# ST_LINK_V2-1.net
KiCad netlist of a schematic drawn in Altium Designer
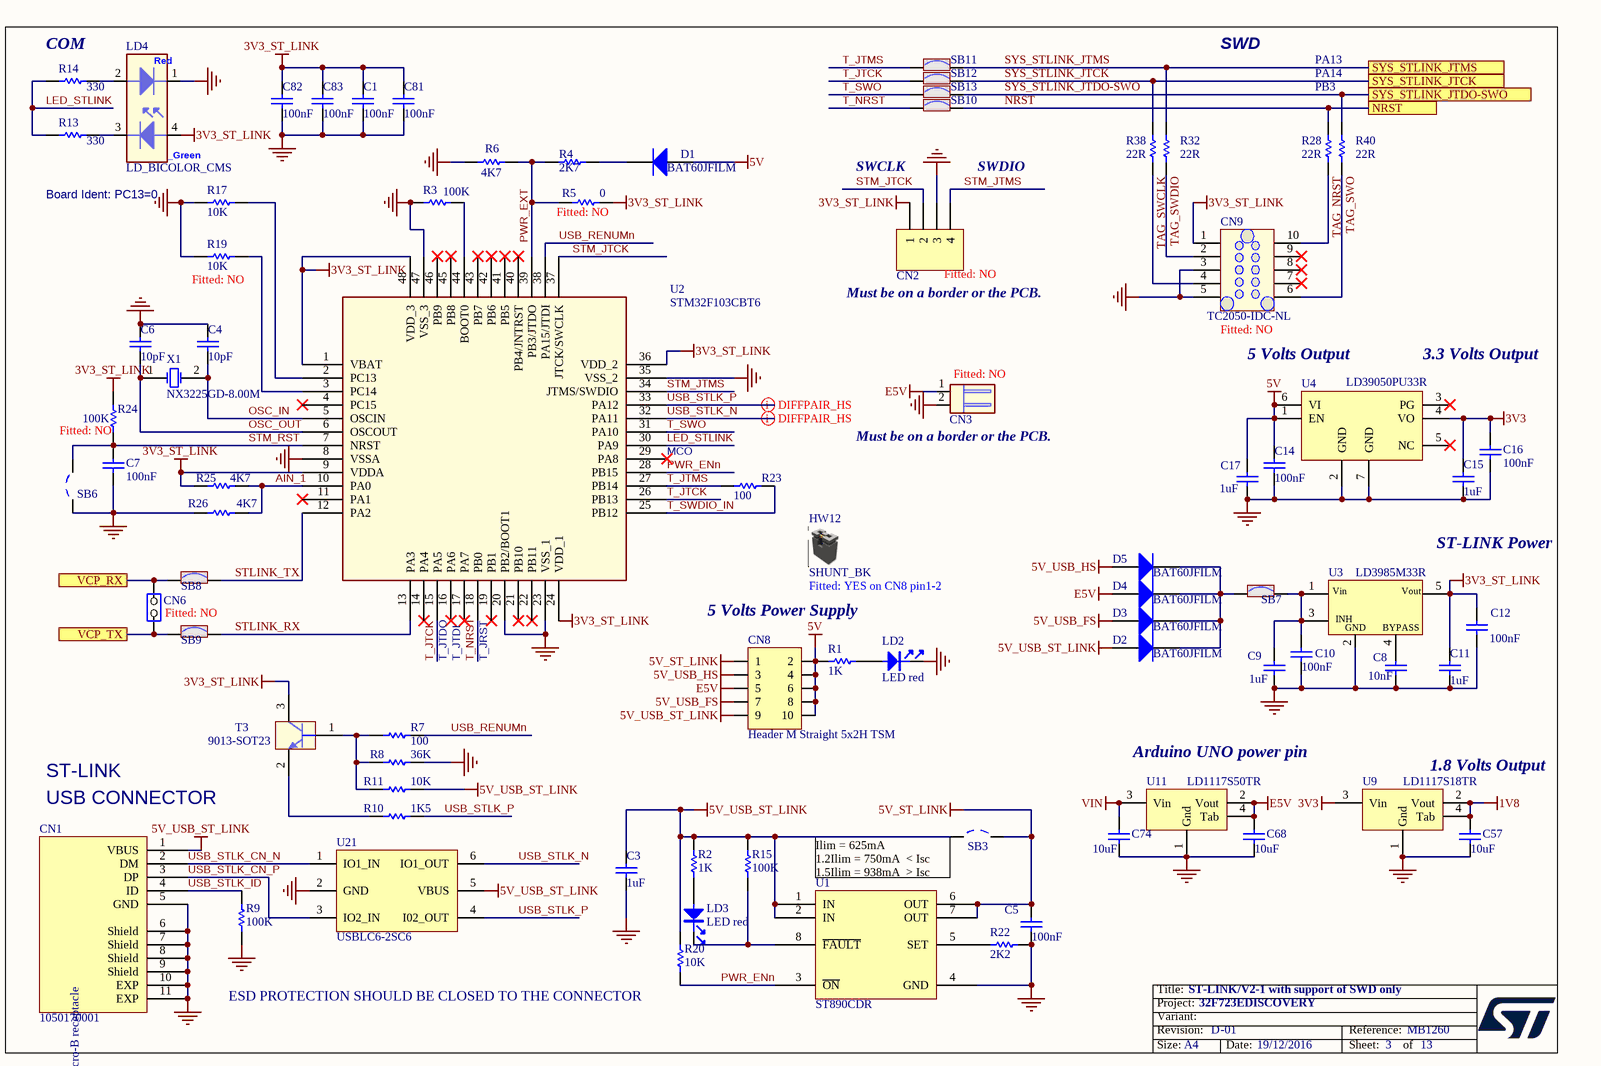
[diagram p0: ST_LINK_V2-1.SCHDOC]

(export (version "E")
  (design (tool "Eeschema 10.0.6"))
  (components
    (comp (ref "C1")
      (value "100nF")
      (footprint "0402C")
      (description "Capacitor,100nF,16V,X7R,10%,0402,YAGEO")
      (libsource (lib "MCD_TOOLS") (part "Cap_100nF_X7R_10%_0402"))
    )
    (comp (ref "C3")
      (value "1uF")
      (footprint "0603C")
      (description "Capacitor,1uF,16V,X5R,10%,0603,YAGEO")
      (libsource (lib "MCD_TOOLS_CAPACITOR") (part "Cap_1uF_X5R_10%_0603"))
    )
    (comp (ref "C4")
      (value "10pF")
      (footprint "0402C")
      (description "Capacitor,10pF,50V,NPO,5%,0402,YAGEO")
      (libsource (lib "MCD_TOOLS") (part "Cap_10pF_NPO_5%_0402"))
    )
    (comp (ref "C5")
      (value "100nF")
      (footprint "0402C")
      (description "Capacitor,100nF,16V,X7R,10%,0402,YAGEO")
      (libsource (lib "MCD_TOOLS") (part "Cap_100nF_X7R_10%_0402"))
    )
    (comp (ref "C6")
      (value "10pF")
      (footprint "0402C")
      (description "Capacitor,10pF,50V,NPO,5%,0402,YAGEO")
      (libsource (lib "MCD_TOOLS") (part "Cap_10pF_NPO_5%_0402"))
    )
    (comp (ref "C7")
      (value "100nF")
      (footprint "0402C")
      (description "Capacitor,100nF,16V,X7R,10%,0402,YAGEO")
      (libsource (lib "MCD_TOOLS") (part "Cap_100nF_X7R_10%_0402"))
    )
    (comp (ref "C8")
      (value "10nF")
      (footprint "0603C")
      (description "Capacitor,10nF,50V,X7R,10%,0603,YAGEO")
      (fields (field (name "Comment") "10nF_X7R_10%_0603"))
      (libsource (lib "MCD_TOOLS_CAPACITOR") (part "Cap_10nF_X7R_10%_0603"))
    )
    (comp (ref "C9")
      (value "1uF")
      (footprint "0603C")
      (description "Capacitor,1uF,16V,X5R,10%,0603,YAGEO")
      (libsource (lib "MCD_TOOLS_CAPACITOR") (part "Cap_1uF_X5R_10%_0603"))
    )
    (comp (ref "C10")
      (value "100nF")
      (footprint "0402C")
      (description "Capacitor,100nF,16V,X7R,10%,0402,YAGEO")
      (libsource (lib "MCD_TOOLS") (part "Cap_100nF_X7R_10%_0402"))
    )
    (comp (ref "C11")
      (value "1uF")
      (footprint "0603C")
      (description "Capacitor,1uF,16V,X5R,10%,0603,YAGEO")
      (libsource (lib "MCD_TOOLS_CAPACITOR") (part "Cap_1uF_X5R_10%_0603"))
    )
    (comp (ref "C12")
      (value "100nF")
      (footprint "0402C")
      (description "Capacitor,100nF,16V,X7R,10%,0402,YAGEO")
      (libsource (lib "MCD_TOOLS") (part "Cap_100nF_X7R_10%_0402"))
    )
    (comp (ref "C14")
      (value "100nF")
      (footprint "0402C")
      (description "Capacitor,100nF,16V,X7R,10%,0402,YAGEO")
      (libsource (lib "MCD_TOOLS") (part "Cap_100nF_X7R_10%_0402"))
    )
    (comp (ref "C15")
      (value "1uF")
      (footprint "0603C")
      (description "Capacitor,1uF,16V,X5R,10%,0603,YAGEO")
      (libsource (lib "MCD_TOOLS_CAPACITOR") (part "Cap_1uF_X5R_10%_0603"))
    )
    (comp (ref "C16")
      (value "100nF")
      (footprint "0402C")
      (description "Capacitor,100nF,16V,X7R,10%,0402,YAGEO")
      (libsource (lib "MCD_TOOLS") (part "Cap_100nF_X7R_10%_0402"))
    )
    (comp (ref "C17")
      (value "1uF")
      (footprint "0603C")
      (description "Capacitor,1uF,16V,X5R,10%,0603,YAGEO")
      (libsource (lib "MCD_TOOLS_CAPACITOR") (part "Cap_1uF_X5R_10%_0603"))
    )
    (comp (ref "C57")
      (value "10uF")
      (footprint "0603C")
      (description "Capacitor,10uF,6.3V,X5R,10%,0603,YAGEO")
      (libsource (lib "MCD_TOOLS") (part "Cap_10uF_X5R_10%_0603"))
    )
    (comp (ref "C68")
      (value "10uF")
      (footprint "0805C")
      (description "Capacitor,10uF,25V,X5R,10%,0805,YAGEO")
      (libsource (lib "MCD_TOOLS") (part "Cap_10uF_X5R_10%_0805"))
    )
    (comp (ref "C74")
      (value "10uF")
      (footprint "0805C")
      (description "Capacitor,10uF,25V,X5R,10%,0805,YAGEO")
      (libsource (lib "MCD_TOOLS") (part "Cap_10uF_X5R_10%_0805"))
    )
    (comp (ref "C81")
      (value "100nF")
      (footprint "0402C")
      (description "Capacitor,100nF,16V,X7R,10%,0402,YAGEO")
      (libsource (lib "MCD_TOOLS") (part "Cap_100nF_X7R_10%_0402"))
    )
    (comp (ref "C82")
      (value "100nF")
      (footprint "0402C")
      (description "Capacitor,100nF,16V,X7R,10%,0402,YAGEO")
      (libsource (lib "MCD_TOOLS") (part "Cap_100nF_X7R_10%_0402"))
    )
    (comp (ref "C83")
      (value "100nF")
      (footprint "0402C")
      (description "Capacitor,100nF,16V,X7R,10%,0402,YAGEO")
      (libsource (lib "MCD_TOOLS") (part "Cap_100nF_X7R_10%_0402"))
    )
    (comp (ref "CN1")
      (value "1050170001")
      (footprint "MICRO_USB_B_105017")
      (description "USB-MICRO-B, 1050170001, SMT, MOLEX")
      (libsource (lib "MCD_TEMP_NPA") (part "1050170001"))
    )
    (comp (ref "CN2")
      (value "Header 4")
      (footprint "HDR_1X4_2R54")
      (description "Header, 4-Pin")
      (fields (field (name "FITTED") "NO") (field (name "PUBLISHER") "Altium Limited"))
      (libsource (lib "MCD_TOOLS_CONNECTOR") (part "Header 4"))
    )
    (comp (ref "CN3")
      (value "WF25402-06421")
      (footprint "HDR_1X2_2R54_RA_11R35")
      (description "Header, 2-Pins, Single row, Right Angle, 2.54 mm pitch, DIP")
      (fields (field (name "FITTED") "NO"))
      (libsource (lib "MCD_TOOLS_CONNECTOR") (part "JP2_RA"))
    )
    (comp (ref "CN6")
      (value "JP2")
      (footprint "SIP2")
      (fields (field (name "FITTED") "NO"))
      (libsource (lib "MCD_TOOLS_CONNECTOR") (part "JP2"))
    )
    (comp (ref "CN8")
      (value "Header M Straight 5x2H TSM")
      (footprint "TSM-105-01-S-DV")
      (description "Header Male TSM, 5-Pin, Dual row, Straight, AMD")
      (libsource (lib "MCD_TEMP_NPA") (part "Header 5X2M TSM"))
    )
    (comp (ref "CN9")
      (value "TC2050-IDC-NL")
      (footprint "TC2050-IDC-NL")
      (description "Tag_Connector Header, 10-Pin, Dual row No legs")
      (fields (field (name "FITTED") "NO"))
      (libsource (lib "MCD_TEMP_PCH") (part "Tag-10-C"))
    )
    (comp (ref "D1")
      (value "BAT60JFILM")
      (footprint "SOD-323")
      (libsource (lib "MCD_TOOLS_MISCELLANEOUS") (part "BAT60JFILM"))
    )
    (comp (ref "D2")
      (value "BAT60JFILM")
      (footprint "SOD-323")
      (libsource (lib "MCD_TOOLS_MISCELLANEOUS") (part "BAT60JFILM"))
    )
    (comp (ref "D3")
      (value "BAT60JFILM")
      (footprint "SOD-323")
      (libsource (lib "MCD_TOOLS_MISCELLANEOUS") (part "BAT60JFILM"))
    )
    (comp (ref "D4")
      (value "BAT60JFILM")
      (footprint "SOD-323")
      (libsource (lib "MCD_TOOLS_MISCELLANEOUS") (part "BAT60JFILM"))
    )
    (comp (ref "D5")
      (value "BAT60JFILM")
      (footprint "SOD-323")
      (libsource (lib "MCD_TOOLS_MISCELLANEOUS") (part "BAT60JFILM"))
    )
    (comp (ref "HW12")
      (value "SHUNT_BK")
      (description "SHUNT 2.54mm BLACK")
      (fields (field (name "FITTED") "YES on CN8 pin1-2"))
      (libsource (lib "MCD_Temp_LBE") (part "Shunt 2.54mm"))
    )
    (comp (ref "LD2")
      (value "LED red")
      (footprint "0603D")
      (description "LED red 0603")
      (libsource (lib "MCD_TEMP_NPA") (part "LED_red"))
    )
    (comp (ref "LD3")
      (value "LED red")
      (footprint "0603D")
      (description "LED red 0603")
      (libsource (lib "MCD_TEMP_NPA") (part "LED_red"))
    )
    (comp (ref "LD4")
      (value "LD_BICOLOR_CMS")
      (footprint "LED2_3528")
      (description "Bicolor Led")
      (libsource (lib "MCD_TOOLS_MISCELLANEOUS") (part "LD_BICOLOR_CMS"))
    )
    (comp (ref "R1")
      (value "1K")
      (footprint "0402R")
      (description "Resistor,1K,0402,1%,YAGEO")
      (libsource (lib "MCD_TOOLS_RESISTOR") (part "Res_1K_1%_0402"))
    )
    (comp (ref "R2")
      (value "1K")
      (footprint "0402R")
      (description "Resistor,1K,0402,1%,YAGEO")
      (libsource (lib "MCD_TOOLS_RESISTOR") (part "Res_1K_1%_0402"))
    )
    (comp (ref "R3")
      (value "100K")
      (footprint "0402R")
      (description "Resistor,100K,0402,1%,YAGEO")
      (fields (field (name "Comment") "100K_1%_0402"))
      (libsource (lib "MCD_TOOLS_RESISTOR") (part "Res_100K_1%_0402"))
    )
    (comp (ref "R4")
      (value "2K7")
      (footprint "0402R")
      (description "Resistor,2K7,0402,1%,YAGEO")
      (libsource (lib "MCD_TOOLS") (part "Res_2K7_1%_0402"))
    )
    (comp (ref "R5")
      (value "0")
      (footprint "0402R")
      (description "Resistor,0,0402,5%,YAGEO")
      (fields (field (name "FITTED") "NO"))
      (libsource (lib "MCD_TOOLS") (part "Res_0_5%_0402"))
    )
    (comp (ref "R6")
      (value "4K7")
      (footprint "0402R")
      (description "Resistor,4K7,0402,1%,YAGEO")
      (fields (field (name "Comment") "4K7_1%_0402"))
      (libsource (lib "MCD_TOOLS_RESISTOR") (part "Res_4K7_1%_0402"))
    )
    (comp (ref "R7")
      (value "100")
      (footprint "0402R")
      (description "Resistor,100,0402,1%,YAGEO")
      (libsource (lib "MCD_TOOLS") (part "Res_100_1%_0402"))
    )
    (comp (ref "R8")
      (value "36K")
      (footprint "0402R")
      (description "Resistor,36K,0402,1%,YAGEO")
      (libsource (lib "MCD_TOOLS") (part "Res_36K_1%_0402"))
    )
    (comp (ref "R9")
      (value "100K")
      (footprint "0402R")
      (description "Resistor,100K,0402,1%,YAGEO")
      (fields (field (name "Comment") "100K_1%_0402"))
      (libsource (lib "MCD_TOOLS_RESISTOR") (part "Res_100K_1%_0402"))
    )
    (comp (ref "R10")
      (value "1K5")
      (footprint "0402R")
      (description "Resistor,1K5,0402,1%,YAGEO")
      (libsource (lib "MCD_TOOLS") (part "Res_1K5_1%_0402"))
    )
    (comp (ref "R11")
      (value "10K")
      (footprint "0402R")
      (description "Resistor,10K,0402,1%,YAGEO")
      (libsource (lib "MCD_TOOLS") (part "Res_10K_1%_0402"))
    )
    (comp (ref "R13")
      (value "330")
      (footprint "0402R")
      (description "Resistor,330,0402,1%,YAGEO")
      (libsource (lib "MCD_TOOLS") (part "Res_330_1%_0402"))
    )
    (comp (ref "R14")
      (value "330")
      (footprint "0402R")
      (description "Resistor,330,0402,1%,YAGEO")
      (libsource (lib "MCD_TOOLS") (part "Res_330_1%_0402"))
    )
    (comp (ref "R15")
      (value "100K")
      (footprint "0402R")
      (description "Resistor,100K,0402,1%,YAGEO")
      (fields (field (name "Comment") "100K_1%_0402"))
      (libsource (lib "MCD_TOOLS_RESISTOR") (part "Res_100K_1%_0402"))
    )
    (comp (ref "R17")
      (value "10K")
      (footprint "0402R")
      (description "Resistor,10K,0402,1%,YAGEO")
      (libsource (lib "MCD_TOOLS") (part "Res_10K_1%_0402"))
    )
    (comp (ref "R19")
      (value "10K")
      (footprint "0402R")
      (description "Resistor,10K,0402,1%,YAGEO")
      (fields (field (name "FITTED") "NO"))
      (libsource (lib "MCD_TOOLS") (part "Res_10K_1%_0402"))
    )
    (comp (ref "R20")
      (value "10K")
      (footprint "0402R")
      (description "Resistor,10K,0402,1%,YAGEO")
      (libsource (lib "MCD_TOOLS") (part "Res_10K_1%_0402"))
    )
    (comp (ref "R22")
      (value "2K2")
      (footprint "0402R")
      (description "Resistor,2K2,0402,1%,YAGEO")
      (libsource (lib "MCD_TOOLS_RESISTOR") (part "Res_2K2_1%_0402"))
    )
    (comp (ref "R23")
      (value "100")
      (footprint "0402R")
      (description "Resistor,100,0402,1%,YAGEO")
      (libsource (lib "MCD_TOOLS") (part "Res_100_1%_0402"))
    )
    (comp (ref "R24")
      (value "100K")
      (footprint "0402R")
      (description "Resistor,100K,0402,1%,YAGEO")
      (fields (field (name "FITTED") "NO") (field (name "Comment") "100K_1%_0402"))
      (libsource (lib "MCD_TOOLS_RESISTOR") (part "Res_100K_1%_0402"))
    )
    (comp (ref "R25")
      (value "4K7")
      (footprint "0402R")
      (description "Resistor,4K7,0402,1%,YAGEO")
      (fields (field (name "Comment") "4K7_1%_0402"))
      (libsource (lib "MCD_TOOLS_RESISTOR") (part "Res_4K7_1%_0402"))
    )
    (comp (ref "R26")
      (value "4K7")
      (footprint "0402R")
      (description "Resistor,4K7,0402,1%,YAGEO")
      (fields (field (name "Comment") "4K7_1%_0402"))
      (libsource (lib "MCD_TOOLS_RESISTOR") (part "Res_4K7_1%_0402"))
    )
    (comp (ref "R28")
      (value "22R")
      (footprint "R0603")
      (description "Resistor,22R,0603,1%,Yageo")
      (libsource (lib "MCD_TEMP_PCH") (part "Res_22_1%_0603"))
    )
    (comp (ref "R32")
      (value "22R")
      (footprint "R0603")
      (description "Resistor,22R,0603,1%,Yageo")
      (libsource (lib "MCD_TEMP_PCH") (part "Res_22_1%_0603"))
    )
    (comp (ref "R38")
      (value "22R")
      (footprint "R0603")
      (description "Resistor,22R,0603,1%,Yageo")
      (libsource (lib "MCD_TEMP_PCH") (part "Res_22_1%_0603"))
    )
    (comp (ref "R40")
      (value "22R")
      (footprint "R0603")
      (description "Resistor,22R,0603,1%,Yageo")
      (libsource (lib "MCD_TEMP_PCH") (part "Res_22_1%_0603"))
    )
    (comp (ref "SB3")
      (value "Solder Bridge OFF")
      (footprint "JP2_SMD")
      (libsource (lib "MCD_TOOLS") (part "SB_OFF"))
    )
    (comp (ref "SB6")
      (value "Solder Bridge OFF")
      (footprint "JP2_SMD")
      (libsource (lib "MCD_TOOLS") (part "SB_OFF"))
    )
    (comp (ref "SB7")
      (value "Solder Bridge ON")
      (footprint "JP2_SMD")
      (libsource (lib "MCD_TOOLS") (part "SB_ON"))
    )
    (comp (ref "SB8")
      (value "Solder Bridge ON")
      (footprint "JP2_SMD")
      (libsource (lib "MCD_TOOLS") (part "SB_ON"))
    )
    (comp (ref "SB9")
      (value "Solder Bridge ON")
      (footprint "JP2_SMD")
      (libsource (lib "MCD_TOOLS") (part "SB_ON"))
    )
    (comp (ref "SB10")
      (value "Solder Bridge ON")
      (footprint "JP2_SMD")
      (libsource (lib "MCD_TOOLS") (part "SB_ON"))
    )
    (comp (ref "SB11")
      (value "Solder Bridge ON")
      (footprint "JP2_SMD")
      (libsource (lib "MCD_TOOLS") (part "SB_ON"))
    )
    (comp (ref "SB12")
      (value "Solder Bridge ON")
      (footprint "JP2_SMD")
      (libsource (lib "MCD_TOOLS") (part "SB_ON"))
    )
    (comp (ref "SB13")
      (value "Solder Bridge ON")
      (footprint "JP2_SMD")
      (libsource (lib "MCD_TOOLS") (part "SB_ON"))
    )
    (comp (ref "T3")
      (value "9013-SOT23")
      (footprint "SOT-23")
      (description "NPN Bipolar Transistor")
      (libsource (lib "MCD_TOOLS_MISCELLANEOUS") (part "9013-SOT23"))
    )
    (comp (ref "U1")
      (value "ST890CDR")
      (footprint "SOIC8_1R27_4R9X6")
      (description "1.2 A current limited high-side power switch with thermal shutdown")
      (libsource (lib "MCD_TEMP_NPA") (part "ST890CDR"))
    )
    (comp (ref "U2")
      (value "STM32F103CBT6")
      (footprint "LQFP48_0R5_9X9")
      (description "Medium-density performance line ARM-based 32-bit MCU with 128KB Flash")
      (libsource (lib "MCD_TOOLS_MCU") (part "STM32F103CBT6"))
    )
    (comp (ref "U3")
      (value "LD3985M33R")
      (footprint "SOT-23-5L")
      (description "Ultra low drop-low noise BiCMOS voltage, regulators low ESR capacitors compatible")
      (libsource (lib "MCD_TOOLS_MISCELLANEOUS") (part "LD3985M33R"))
    )
    (comp (ref "U4")
      (value "LD39050PU33R")
      (footprint "DFN6_0R95_3X3")
      (description "Ultra low drop-low , 500 mA low quiescent current")
      (libsource (lib "MCD_TEMP_NPA") (part "LD39050P"))
    )
    (comp (ref "U9")
      (value "LD1117S18TR")
      (footprint "SOT-223")
      (description "LOW DROP FIXED AND ADJUSTABLE POSITIVE VOLTAGE REGULATORS (1.8 Volts)")
      (libsource (lib "MCD_TEMP_NPA") (part "LD1117S18TR"))
    )
    (comp (ref "U11")
      (value "LD1117S50TR")
      (footprint "SOT-223")
      (description "IC REG LDO 5V 0.8A SOT223")
      (libsource (lib "MCD_TEMP_NPA") (part "LD1117S50TR"))
    )
    (comp (ref "U21")
      (value "USBLC6-2SC6")
      (footprint "SOT23-6")
      (description "Very low capacitance ESD protection")
      (libsource (lib "MCD_TEMP_NPA") (part "USBLC6-2SC6"))
    )
    (comp (ref "X1")
      (value "NX3225GD-8.00M")
      (footprint "XTAL_2SM_3R2X2R5_H1")
      (description "Crystal 8Mhz, 8pF, -+50PPM, SMD")
      (libsource (lib "MCD_TEMP_NPA") (part "XTAL_8M_NX3225GD"))
    )
  )
  (nets
    (net (code "1") (name "/AIN_1") (class "Default")
      (node (ref "R25") (pin "2") (pinfunction "2_2") (pintype "passive"))
      (node (ref "R26") (pin "2") (pinfunction "2_2") (pintype "passive"))
      (node (ref "U2") (pin "10") (pinfunction "PA0_10") (pintype "passive"))
    )
    (net (code "2") (name "/LED_STLINK") (class "Default")
      (node (ref "R13") (pin "1") (pinfunction "1_1") (pintype "passive"))
      (node (ref "R14") (pin "1") (pinfunction "1_1") (pintype "passive"))
      (node (ref "U2") (pin "30") (pinfunction "PA9_30") (pintype "passive"))
    )
    (net (code "3") (name "/NRST") (class "Default")
      (node (ref "R28") (pin "2") (pinfunction "2_2") (pintype "passive"))
      (node (ref "SB10") (pin "2") (pinfunction "2_2") (pintype "passive"))
    )
    (net (code "4") (name "/OSC_IN") (class "Default")
      (node (ref "C4") (pin "2") (pinfunction "2_2") (pintype "passive"))
      (node (ref "U2") (pin "5") (pinfunction "OSCIN_5") (pintype "passive"))
      (node (ref "X1") (pin "2") (pinfunction "OSC2_2") (pintype "passive"))
    )
    (net (code "5") (name "/OSC_OUT") (class "Default")
      (node (ref "C6") (pin "2") (pinfunction "2_2") (pintype "passive"))
      (node (ref "U2") (pin "6") (pinfunction "OSCOUT_6") (pintype "passive"))
      (node (ref "X1") (pin "1") (pinfunction "OSC1_1") (pintype "passive"))
    )
    (net (code "6") (name "/PWR_ENn") (class "Default")
      (node (ref "R20") (pin "1") (pinfunction "1_1") (pintype "passive"))
      (node (ref "U1") (pin "3") (pinfunction "~{ON}_3") (pintype "passive"))
      (node (ref "U2") (pin "28") (pinfunction "PB15_28") (pintype "passive"))
    )
    (net (code "7") (name "/PWR_EXT") (class "Default")
      (node (ref "R4") (pin "1") (pinfunction "1_1") (pintype "passive"))
      (node (ref "R5") (pin "1") (pinfunction "1_1") (pintype "passive"))
      (node (ref "R6") (pin "2") (pinfunction "2_2") (pintype "passive"))
      (node (ref "U2") (pin "39") (pinfunction "PB3/JTDO_39") (pintype "passive"))
    )
    (net (code "8") (name "/STLINK_RX") (class "Default")
      (node (ref "SB9") (pin "2") (pinfunction "2_2") (pintype "passive"))
      (node (ref "U2") (pin "13") (pinfunction "PA3_13") (pintype "passive"))
    )
    (net (code "9") (name "/STLINK_TX") (class "Default")
      (node (ref "SB8") (pin "2") (pinfunction "2_2") (pintype "passive"))
      (node (ref "U2") (pin "12") (pinfunction "PA2_12") (pintype "passive"))
    )
    (net (code "10") (name "/STM_JTCK") (class "Default")
      (node (ref "CN2") (pin "2") (pinfunction "2_2") (pintype "passive"))
      (node (ref "U2") (pin "37") (pinfunction "JTCK/SWCLK_37") (pintype "passive"))
    )
    (net (code "11") (name "/STM_JTMS") (class "Default")
      (node (ref "CN2") (pin "4") (pinfunction "4_4") (pintype "passive"))
      (node (ref "U2") (pin "34") (pinfunction "JTMS/SWDIO_34") (pintype "passive"))
    )
    (net (code "12") (name "/STM_RST") (class "Default")
      (node (ref "C7") (pin "2") (pinfunction "2_2") (pintype "passive"))
      (node (ref "R24") (pin "1") (pinfunction "1_1") (pintype "passive"))
      (node (ref "SB6") (pin "2") (pinfunction "2_2") (pintype "passive"))
      (node (ref "U2") (pin "7") (pinfunction "NRST_7") (pintype "passive"))
    )
    (net (code "13") (name "/SYS_STLINK_JTCK") (class "Default")
      (node (ref "R38") (pin "2") (pinfunction "2_2") (pintype "passive"))
      (node (ref "SB12") (pin "2") (pinfunction "2_2") (pintype "passive"))
    )
    (net (code "14") (name "/SYS_STLINK_JTDO-SWO") (class "Default")
      (node (ref "R40") (pin "2") (pinfunction "2_2") (pintype "passive"))
      (node (ref "SB13") (pin "2") (pinfunction "2_2") (pintype "passive"))
    )
    (net (code "15") (name "/SYS_STLINK_JTMS") (class "Default")
      (node (ref "R32") (pin "2") (pinfunction "2_2") (pintype "passive"))
      (node (ref "SB11") (pin "2") (pinfunction "2_2") (pintype "passive"))
    )
    (net (code "16") (name "/TAG_NRST") (class "Default")
      (node (ref "CN9") (pin "10") (pinfunction "10_10") (pintype "passive"))
      (node (ref "R28") (pin "1") (pinfunction "1_1") (pintype "passive"))
    )
    (net (code "17") (name "/TAG_SWCLK") (class "Default")
      (node (ref "CN9") (pin "4") (pinfunction "4_4") (pintype "passive"))
      (node (ref "R38") (pin "1") (pinfunction "1_1") (pintype "passive"))
    )
    (net (code "18") (name "/TAG_SWDIO") (class "Default")
      (node (ref "CN9") (pin "2") (pinfunction "2_2") (pintype "passive"))
      (node (ref "R32") (pin "1") (pinfunction "1_1") (pintype "passive"))
    )
    (net (code "19") (name "/TAG_SWO") (class "Default")
      (node (ref "CN9") (pin "6") (pinfunction "6_6") (pintype "passive"))
      (node (ref "R40") (pin "1") (pinfunction "1_1") (pintype "passive"))
    )
    (net (code "20") (name "/T_JTCK") (class "Default")
      (node (ref "SB12") (pin "1") (pinfunction "1_1") (pintype "passive"))
      (node (ref "U2") (pin "15") (pinfunction "PA5_15") (pintype "passive"))
      (node (ref "U2") (pin "26") (pinfunction "PB13_26") (pintype "passive"))
    )
    (net (code "21") (name "/T_JTMS") (class "Default")
      (node (ref "R23") (pin "1") (pinfunction "1_1") (pintype "passive"))
      (node (ref "SB11") (pin "1") (pinfunction "1_1") (pintype "passive"))
      (node (ref "U2") (pin "27") (pinfunction "PB14_27") (pintype "passive"))
    )
    (net (code "22") (name "/T_NRST") (class "Default")
      (node (ref "SB10") (pin "1") (pinfunction "1_1") (pintype "passive"))
      (node (ref "U2") (pin "18") (pinfunction "PB0_18") (pintype "passive"))
    )
    (net (code "23") (name "/T_SWDIO_IN") (class "Default")
      (node (ref "R23") (pin "2") (pinfunction "2_2") (pintype "passive"))
      (node (ref "U2") (pin "25") (pinfunction "PB12_25") (pintype "passive"))
    )
    (net (code "24") (name "/T_SWO") (class "Default")
      (node (ref "SB13") (pin "1") (pinfunction "1_1") (pintype "passive"))
      (node (ref "U2") (pin "31") (pinfunction "PA10_31") (pintype "passive"))
    )
    (net (code "25") (name "/USB_RENUMn") (class "Default")
      (node (ref "R7") (pin "2") (pinfunction "2_2") (pintype "passive"))
      (node (ref "U2") (pin "38") (pinfunction "PA15/JTDI_38") (pintype "passive"))
    )
    (net (code "26") (name "/USB_STLK_CN_N") (class "Default")
      (node (ref "CN1") (pin "2") (pinfunction "DM_2") (pintype "passive"))
      (node (ref "U21") (pin "1") (pinfunction "IO1_IN_1") (pintype "passive"))
    )
    (net (code "27") (name "/USB_STLK_CN_P") (class "Default")
      (node (ref "CN1") (pin "3") (pinfunction "DP_3") (pintype "passive"))
      (node (ref "U21") (pin "3") (pinfunction "IO2_IN_3") (pintype "passive"))
    )
    (net (code "28") (name "/USB_STLK_ID") (class "Default")
      (node (ref "CN1") (pin "4") (pinfunction "ID_4") (pintype "passive"))
      (node (ref "R9") (pin "2") (pinfunction "2_2") (pintype "passive"))
    )
    (net (code "29") (name "/USB_STLK_N") (class "Default")
      (node (ref "U2") (pin "32") (pinfunction "PA11_32") (pintype "passive"))
      (node (ref "U21") (pin "6") (pinfunction "IO1_OUT_6") (pintype "passive"))
    )
    (net (code "30") (name "/USB_STLK_P") (class "Default")
      (node (ref "R10") (pin "2") (pinfunction "2_2") (pintype "passive"))
      (node (ref "U2") (pin "33") (pinfunction "PA12_33") (pintype "passive"))
      (node (ref "U21") (pin "4") (pinfunction "I02_OUT_4") (pintype "passive"))
    )
    (net (code "31") (name "/VCP_RX") (class "Default")
      (node (ref "CN6") (pin "2") (pinfunction "NO_2") (pintype "passive"))
      (node (ref "SB8") (pin "1") (pinfunction "1_1") (pintype "passive"))
    )
    (net (code "32") (name "/VCP_TX") (class "Default")
      (node (ref "CN6") (pin "1") (pinfunction "COMMON_1") (pintype "passive"))
      (node (ref "SB9") (pin "1") (pinfunction "1_1") (pintype "passive"))
    )
    (net (code "33") (name "1V8") (class "Default")
      (node (ref "C57") (pin "2") (pinfunction "2_2") (pintype "passive"))
      (node (ref "U9") (pin "2") (pinfunction "Vout_2") (pintype "passive"))
      (node (ref "U9") (pin "4") (pinfunction "Tab_4") (pintype "passive"))
    )
    (net (code "34") (name "3V3") (class "Default")
      (node (ref "C15") (pin "2") (pinfunction "2_2") (pintype "passive"))
      (node (ref "C16") (pin "2") (pinfunction "2_2") (pintype "passive"))
      (node (ref "U4") (pin "4") (pinfunction "VO_4") (pintype "passive"))
      (node (ref "U9") (pin "3") (pinfunction "Vin_3") (pintype "passive"))
    )
    (net (code "35") (name "3V3_ST_LINK") (class "Default")
      (node (ref "C1") (pin "1") (pinfunction "1_1") (pintype "passive"))
      (node (ref "C11") (pin "2") (pinfunction "2_2") (pintype "passive"))
      (node (ref "C12") (pin "2") (pinfunction "2_2") (pintype "passive"))
      (node (ref "C81") (pin "2") (pinfunction "2_2") (pintype "passive"))
      (node (ref "C82") (pin "2") (pinfunction "2_2") (pintype "passive"))
      (node (ref "C83") (pin "2") (pinfunction "2_2") (pintype "passive"))
      (node (ref "CN2") (pin "1") (pinfunction "1_1") (pintype "passive"))
      (node (ref "CN9") (pin "1") (pinfunction "1_1") (pintype "passive"))
      (node (ref "LD4") (pin "4") (pinfunction "4_4") (pintype "passive"))
      (node (ref "R24") (pin "2") (pinfunction "2_2") (pintype "passive"))
      (node (ref "R25") (pin "1") (pinfunction "1_1") (pintype "passive"))
      (node (ref "R5") (pin "2") (pinfunction "2_2") (pintype "passive"))
      (node (ref "T3") (pin "3") (pinfunction "C_3") (pintype "passive"))
      (node (ref "U2") (pin "1") (pinfunction "VBAT_1") (pintype "passive"))
      (node (ref "U2") (pin "24") (pinfunction "VDD_1_24") (pintype "passive"))
      (node (ref "U2") (pin "36") (pinfunction "VDD_2_36") (pintype "passive"))
      (node (ref "U2") (pin "48") (pinfunction "VDD_3_48") (pintype "passive"))
      (node (ref "U2") (pin "9") (pinfunction "VDDA_9") (pintype "passive"))
      (node (ref "U3") (pin "5") (pinfunction "Vout_5") (pintype "passive"))
    )
    (net (code "36") (name "5V") (class "Default")
      (node (ref "C14") (pin "2") (pinfunction "2_2") (pintype "passive"))
      (node (ref "C17") (pin "2") (pinfunction "2_2") (pintype "passive"))
      (node (ref "CN8") (pin "10") (pinfunction "10_10") (pintype "passive"))
      (node (ref "CN8") (pin "2") (pinfunction "2_2") (pintype "passive"))
      (node (ref "CN8") (pin "4") (pinfunction "4_4") (pintype "passive"))
      (node (ref "CN8") (pin "6") (pinfunction "6_6") (pintype "passive"))
      (node (ref "CN8") (pin "8") (pinfunction "8_8") (pintype "passive"))
      (node (ref "D1") (pin "1") (pinfunction "A_1") (pintype "passive"))
      (node (ref "R1") (pin "1") (pinfunction "1_1") (pintype "passive"))
      (node (ref "U4") (pin "1") (pinfunction "EN_1") (pintype "passive"))
      (node (ref "U4") (pin "6") (pinfunction "VI_6") (pintype "passive"))
    )
    (net (code "37") (name "5V_ST_LINK") (class "Default")
      (node (ref "C5") (pin "2") (pinfunction "2_2") (pintype "passive"))
      (node (ref "CN8") (pin "1") (pinfunction "1_1") (pintype "passive"))
      (node (ref "SB3") (pin "2") (pinfunction "2_2") (pintype "passive"))
      (node (ref "U1") (pin "6") (pinfunction "OUT_6") (pintype "passive"))
      (node (ref "U1") (pin "7") (pinfunction "OUT_7") (pintype "passive"))
    )
    (net (code "38") (name "5V_USB_FS") (class "Default")
      (node (ref "CN8") (pin "7") (pinfunction "7_7") (pintype "passive"))
      (node (ref "D3") (pin "1") (pinfunction "A_1") (pintype "passive"))
    )
    (net (code "39") (name "5V_USB_HS") (class "Default")
      (node (ref "CN8") (pin "3") (pinfunction "3_3") (pintype "passive"))
      (node (ref "D5") (pin "1") (pinfunction "A_1") (pintype "passive"))
    )
    (net (code "40") (name "5V_USB_ST_LINK") (class "Default")
      (node (ref "C3") (pin "2") (pinfunction "2_2") (pintype "passive"))
      (node (ref "CN1") (pin "1") (pinfunction "VBUS_1") (pintype "passive"))
      (node (ref "CN8") (pin "9") (pinfunction "9_9") (pintype "passive"))
      (node (ref "D2") (pin "1") (pinfunction "A_1") (pintype "passive"))
      (node (ref "R11") (pin "1") (pinfunction "1_1") (pintype "passive"))
      (node (ref "R15") (pin "2") (pinfunction "2_2") (pintype "passive"))
      (node (ref "R2") (pin "2") (pinfunction "2_2") (pintype "passive"))
      (node (ref "R20") (pin "2") (pinfunction "2_2") (pintype "passive"))
      (node (ref "SB3") (pin "1") (pinfunction "1_1") (pintype "passive"))
      (node (ref "U1") (pin "1") (pinfunction "IN_1") (pintype "passive"))
      (node (ref "U1") (pin "2") (pinfunction "IN_2") (pintype "passive"))
      (node (ref "U21") (pin "5") (pinfunction "VBUS_5") (pintype "passive"))
    )
    (net (code "41") (name "E5V") (class "Default")
      (node (ref "C68") (pin "2") (pinfunction "2_2") (pintype "passive"))
      (node (ref "CN3") (pin "1") (pinfunction "1_1") (pintype "passive"))
      (node (ref "CN8") (pin "5") (pinfunction "5_5") (pintype "passive"))
      (node (ref "D4") (pin "1") (pinfunction "A_1") (pintype "passive"))
      (node (ref "U11") (pin "2") (pinfunction "Vout_2") (pintype "passive"))
      (node (ref "U11") (pin "4") (pinfunction "Tab_4") (pintype "passive"))
    )
    (net (code "42") (name "GND") (class "Default")
      (node (ref "C1") (pin "2") (pinfunction "2_2") (pintype "passive"))
      (node (ref "C10") (pin "1") (pinfunction "1_1") (pintype "passive"))
      (node (ref "C11") (pin "1") (pinfunction "1_1") (pintype "passive"))
      (node (ref "C12") (pin "1") (pinfunction "1_1") (pintype "passive"))
      (node (ref "C14") (pin "1") (pinfunction "1_1") (pintype "passive"))
      (node (ref "C15") (pin "1") (pinfunction "1_1") (pintype "passive"))
      (node (ref "C16") (pin "1") (pinfunction "1_1") (pintype "passive"))
      (node (ref "C17") (pin "1") (pinfunction "1_1") (pintype "passive"))
      (node (ref "C3") (pin "1") (pinfunction "1_1") (pintype "passive"))
      (node (ref "C4") (pin "1") (pinfunction "1_1") (pintype "passive"))
      (node (ref "C5") (pin "1") (pinfunction "1_1") (pintype "passive"))
      (node (ref "C57") (pin "1") (pinfunction "1_1") (pintype "passive"))
      (node (ref "C6") (pin "1") (pinfunction "1_1") (pintype "passive"))
      (node (ref "C68") (pin "1") (pinfunction "1_1") (pintype "passive"))
      (node (ref "C7") (pin "1") (pinfunction "1_1") (pintype "passive"))
      (node (ref "C74") (pin "1") (pinfunction "1_1") (pintype "passive"))
      (node (ref "C8") (pin "1") (pinfunction "1_1") (pintype "passive"))
      (node (ref "C81") (pin "1") (pinfunction "1_1") (pintype "passive"))
      (node (ref "C82") (pin "1") (pinfunction "1_1") (pintype "passive"))
      (node (ref "C83") (pin "1") (pinfunction "1_1") (pintype "passive"))
      (node (ref "C9") (pin "1") (pinfunction "1_1") (pintype "passive"))
      (node (ref "CN1") (pin "10") (pinfunction "EXP_10") (pintype "passive"))
      (node (ref "CN1") (pin "11") (pinfunction "EXP_11") (pintype "passive"))
      (node (ref "CN1") (pin "5") (pinfunction "GND_5") (pintype "passive"))
      (node (ref "CN1") (pin "6") (pinfunction "Shield_6") (pintype "passive"))
      (node (ref "CN1") (pin "7") (pinfunction "Shield_7") (pintype "passive"))
      (node (ref "CN1") (pin "8") (pinfunction "Shield_8") (pintype "passive"))
      (node (ref "CN1") (pin "9") (pinfunction "Shield_9") (pintype "passive"))
      (node (ref "CN2") (pin "3") (pinfunction "3_3") (pintype "passive"))
      (node (ref "CN3") (pin "2") (pinfunction "2_2") (pintype "passive"))
      (node (ref "CN9") (pin "3") (pinfunction "3_3") (pintype "passive"))
      (node (ref "CN9") (pin "5") (pinfunction "5_5") (pintype "passive"))
      (node (ref "LD2") (pin "2") (pintype "passive"))
      (node (ref "LD4") (pin "1") (pinfunction "1_1") (pintype "passive"))
      (node (ref "R17") (pin "1") (pinfunction "1_1") (pintype "passive"))
      (node (ref "R19") (pin "1") (pinfunction "1_1") (pintype "passive"))
      (node (ref "R22") (pin "2") (pinfunction "2_2") (pintype "passive"))
      (node (ref "R26") (pin "1") (pinfunction "1_1") (pintype "passive"))
      (node (ref "R3") (pin "1") (pinfunction "1_1") (pintype "passive"))
      (node (ref "R6") (pin "1") (pinfunction "1_1") (pintype "passive"))
      (node (ref "R8") (pin "1") (pinfunction "1_1") (pintype "passive"))
      (node (ref "R9") (pin "1") (pinfunction "1_1") (pintype "passive"))
      (node (ref "SB6") (pin "1") (pinfunction "1_1") (pintype "passive"))
      (node (ref "U1") (pin "4") (pinfunction "GND_4") (pintype "passive"))
      (node (ref "U11") (pin "1") (pinfunction "Gnd_1") (pintype "passive"))
      (node (ref "U2") (pin "20") (pinfunction "PB2/BOOT1_20") (pintype "passive"))
      (node (ref "U2") (pin "23") (pinfunction "VSS_1_23") (pintype "passive"))
      (node (ref "U2") (pin "35") (pinfunction "VSS_2_35") (pintype "passive"))
      (node (ref "U2") (pin "47") (pinfunction "VSS_3_47") (pintype "passive"))
      (node (ref "U2") (pin "8") (pinfunction "VSSA_8") (pintype "passive"))
      (node (ref "U21") (pin "2") (pinfunction "GND_2") (pintype "passive"))
      (node (ref "U3") (pin "2") (pinfunction "GND_2") (pintype "passive"))
      (node (ref "U4") (pin "2") (pinfunction "GND_2") (pintype "passive"))
      (node (ref "U4") (pin "7") (pinfunction "GND_7") (pintype "passive"))
      (node (ref "U9") (pin "1") (pinfunction "Gnd_1") (pintype "passive"))
    )
    (net (code "43") (name "Net-(D1-K)") (class "Default")
      (node (ref "D1") (pin "2") (pinfunction "K_2") (pintype "passive"))
      (node (ref "R4") (pin "2") (pinfunction "2_2") (pintype "passive"))
    )
    (net (code "44") (name "Net-(D2-K)") (class "Default")
      (node (ref "D2") (pin "2") (pinfunction "K_2") (pintype "passive"))
      (node (ref "D3") (pin "2") (pinfunction "K_2") (pintype "passive"))
      (node (ref "D4") (pin "2") (pinfunction "K_2") (pintype "passive"))
      (node (ref "D5") (pin "2") (pinfunction "K_2") (pintype "passive"))
      (node (ref "SB7") (pin "1") (pinfunction "1_1") (pintype "passive"))
    )
    (net (code "45") (name "Net-(LD2-Pad1)") (class "Default")
      (node (ref "LD2") (pin "1") (pintype "passive"))
      (node (ref "R1") (pin "2") (pinfunction "2_2") (pintype "passive"))
    )
    (net (code "46") (name "Net-(LD3-Pad1)") (class "Default")
      (node (ref "LD3") (pin "1") (pintype "passive"))
      (node (ref "R2") (pin "1") (pinfunction "1_1") (pintype "passive"))
    )
    (net (code "47") (name "Net-(LD4-Pad2)") (class "Default")
      (node (ref "LD4") (pin "2") (pinfunction "2_2") (pintype "passive"))
      (node (ref "R14") (pin "2") (pinfunction "2_2") (pintype "passive"))
    )
    (net (code "48") (name "Net-(LD4-Pad3)") (class "Default")
      (node (ref "LD4") (pin "3") (pinfunction "3_3") (pintype "passive"))
      (node (ref "R13") (pin "2") (pinfunction "2_2") (pintype "passive"))
    )
    (net (code "49") (name "Net-(T3-B)") (class "Default")
      (node (ref "R11") (pin "2") (pinfunction "2_2") (pintype "passive"))
      (node (ref "R7") (pin "1") (pinfunction "1_1") (pintype "passive"))
      (node (ref "R8") (pin "2") (pinfunction "2_2") (pintype "passive"))
      (node (ref "T3") (pin "1") (pinfunction "B_1") (pintype "passive"))
    )
    (net (code "50") (name "Net-(T3-E)") (class "Default")
      (node (ref "R10") (pin "1") (pinfunction "1_1") (pintype "passive"))
      (node (ref "T3") (pin "2") (pinfunction "E_2") (pintype "passive"))
    )
    (net (code "51") (name "Net-(U1-SET)") (class "Default")
      (node (ref "R22") (pin "1") (pinfunction "1_1") (pintype "passive"))
      (node (ref "U1") (pin "5") (pinfunction "SET_5") (pintype "passive"))
    )
    (net (code "52") (name "Net-(U1-~{FAULT})") (class "Default")
      (node (ref "LD3") (pin "2") (pintype "passive"))
      (node (ref "R15") (pin "1") (pinfunction "1_1") (pintype "passive"))
      (node (ref "U1") (pin "8") (pinfunction "~{FAULT}_8") (pintype "passive"))
    )
    (net (code "53") (name "Net-(U2-BOOT0)") (class "Default")
      (node (ref "R3") (pin "2") (pinfunction "2_2") (pintype "passive"))
      (node (ref "U2") (pin "44") (pinfunction "BOOT0_44") (pintype "passive"))
    )
    (net (code "54") (name "Net-(U2-PC13)") (class "Default")
      (node (ref "R17") (pin "2") (pinfunction "2_2") (pintype "passive"))
      (node (ref "U2") (pin "2") (pinfunction "PC13_2") (pintype "passive"))
    )
    (net (code "55") (name "Net-(U2-PC14)") (class "Default")
      (node (ref "R19") (pin "2") (pinfunction "2_2") (pintype "passive"))
      (node (ref "U2") (pin "3") (pinfunction "PC14_3") (pintype "passive"))
    )
    (net (code "56") (name "Net-(U3-BYPASS)") (class "Default")
      (node (ref "C8") (pin "2") (pinfunction "2_2") (pintype "passive"))
      (node (ref "U3") (pin "4") (pinfunction "BYPASS_4") (pintype "passive"))
    )
    (net (code "57") (name "Net-(U3-CE)") (class "Default")
      (node (ref "C10") (pin "2") (pinfunction "2_2") (pintype "passive"))
      (node (ref "C9") (pin "2") (pinfunction "2_2") (pintype "passive"))
      (node (ref "SB7") (pin "2") (pinfunction "2_2") (pintype "passive"))
      (node (ref "U3") (pin "1") (pinfunction "Vin_1") (pintype "passive"))
      (node (ref "U3") (pin "3") (pinfunction "CE_3") (pintype "passive"))
    )
    (net (code "58") (name "VIN") (class "Default")
      (node (ref "C74") (pin "2") (pinfunction "2_2") (pintype "passive"))
      (node (ref "U11") (pin "3") (pinfunction "Vin_3") (pintype "passive"))
    )
    (net (code "59") (name "unconnected-(CN9-Pad7)") (class "Default")
      (node (ref "CN9") (pin "7") (pinfunction "7_7") (pintype "passive+no_connect"))
    )
    (net (code "60") (name "unconnected-(CN9-Pad8)") (class "Default")
      (node (ref "CN9") (pin "8") (pinfunction "8_8") (pintype "passive+no_connect"))
    )
    (net (code "61") (name "unconnected-(CN9-Pad9)") (class "Default")
      (node (ref "CN9") (pin "9") (pinfunction "9_9") (pintype "passive+no_connect"))
    )
    (net (code "62") (name "unconnected-(U2-PA1-Pad11)") (class "Default")
      (node (ref "U2") (pin "11") (pinfunction "PA1_11") (pintype "passive+no_connect"))
    )
    (net (code "63") (name "unconnected-(U2-PA4-Pad14)") (class "Default")
      (node (ref "U2") (pin "14") (pinfunction "PA4_14") (pintype "passive+no_connect"))
    )
    (net (code "64") (name "unconnected-(U2-PA6-Pad16)") (class "Default")
      (node (ref "U2") (pin "16") (pinfunction "PA6_16") (pintype "passive+no_connect"))
    )
    (net (code "65") (name "unconnected-(U2-PA7-Pad17)") (class "Default")
      (node (ref "U2") (pin "17") (pinfunction "PA7_17") (pintype "passive+no_connect"))
    )
    (net (code "66") (name "unconnected-(U2-PA8-Pad29)") (class "Default")
      (node (ref "U2") (pin "29") (pinfunction "PA8_29") (pintype "passive+no_connect"))
    )
    (net (code "67") (name "unconnected-(U2-PB1-Pad19)") (class "Default")
      (node (ref "U2") (pin "19") (pinfunction "PB1_19") (pintype "passive+no_connect"))
    )
    (net (code "68") (name "unconnected-(U2-PB4{slash}JNTRST-Pad40)") (class "Default")
      (node (ref "U2") (pin "40") (pinfunction "PB4/JNTRST_40") (pintype "passive+no_connect"))
    )
    (net (code "69") (name "unconnected-(U2-PB5-Pad41)") (class "Default")
      (node (ref "U2") (pin "41") (pinfunction "PB5_41") (pintype "passive+no_connect"))
    )
    (net (code "70") (name "unconnected-(U2-PB6-Pad42)") (class "Default")
      (node (ref "U2") (pin "42") (pinfunction "PB6_42") (pintype "passive+no_connect"))
    )
    (net (code "71") (name "unconnected-(U2-PB7-Pad43)") (class "Default")
      (node (ref "U2") (pin "43") (pinfunction "PB7_43") (pintype "passive+no_connect"))
    )
    (net (code "72") (name "unconnected-(U2-PB8-Pad45)") (class "Default")
      (node (ref "U2") (pin "45") (pinfunction "PB8_45") (pintype "passive+no_connect"))
    )
    (net (code "73") (name "unconnected-(U2-PB9-Pad46)") (class "Default")
      (node (ref "U2") (pin "46") (pinfunction "PB9_46") (pintype "passive+no_connect"))
    )
    (net (code "74") (name "unconnected-(U2-PB10-Pad21)") (class "Default")
      (node (ref "U2") (pin "21") (pinfunction "PB10_21") (pintype "passive+no_connect"))
    )
    (net (code "75") (name "unconnected-(U2-PB11-Pad22)") (class "Default")
      (node (ref "U2") (pin "22") (pinfunction "PB11_22") (pintype "passive+no_connect"))
    )
    (net (code "76") (name "unconnected-(U2-PC15-Pad4)") (class "Default")
      (node (ref "U2") (pin "4") (pinfunction "PC15_4") (pintype "passive+no_connect"))
    )
    (net (code "77") (name "unconnected-(U4-NC-Pad5)") (class "Default")
      (node (ref "U4") (pin "5") (pinfunction "NC_5") (pintype "passive+no_connect"))
    )
    (net (code "78") (name "unconnected-(U4-PG-Pad3)") (class "Default")
      (node (ref "U4") (pin "3") (pinfunction "PG_3") (pintype "passive+no_connect"))
    )
  )
)
